# injector_C.net
KiCad netlist of a schematic drawn in EAGLE
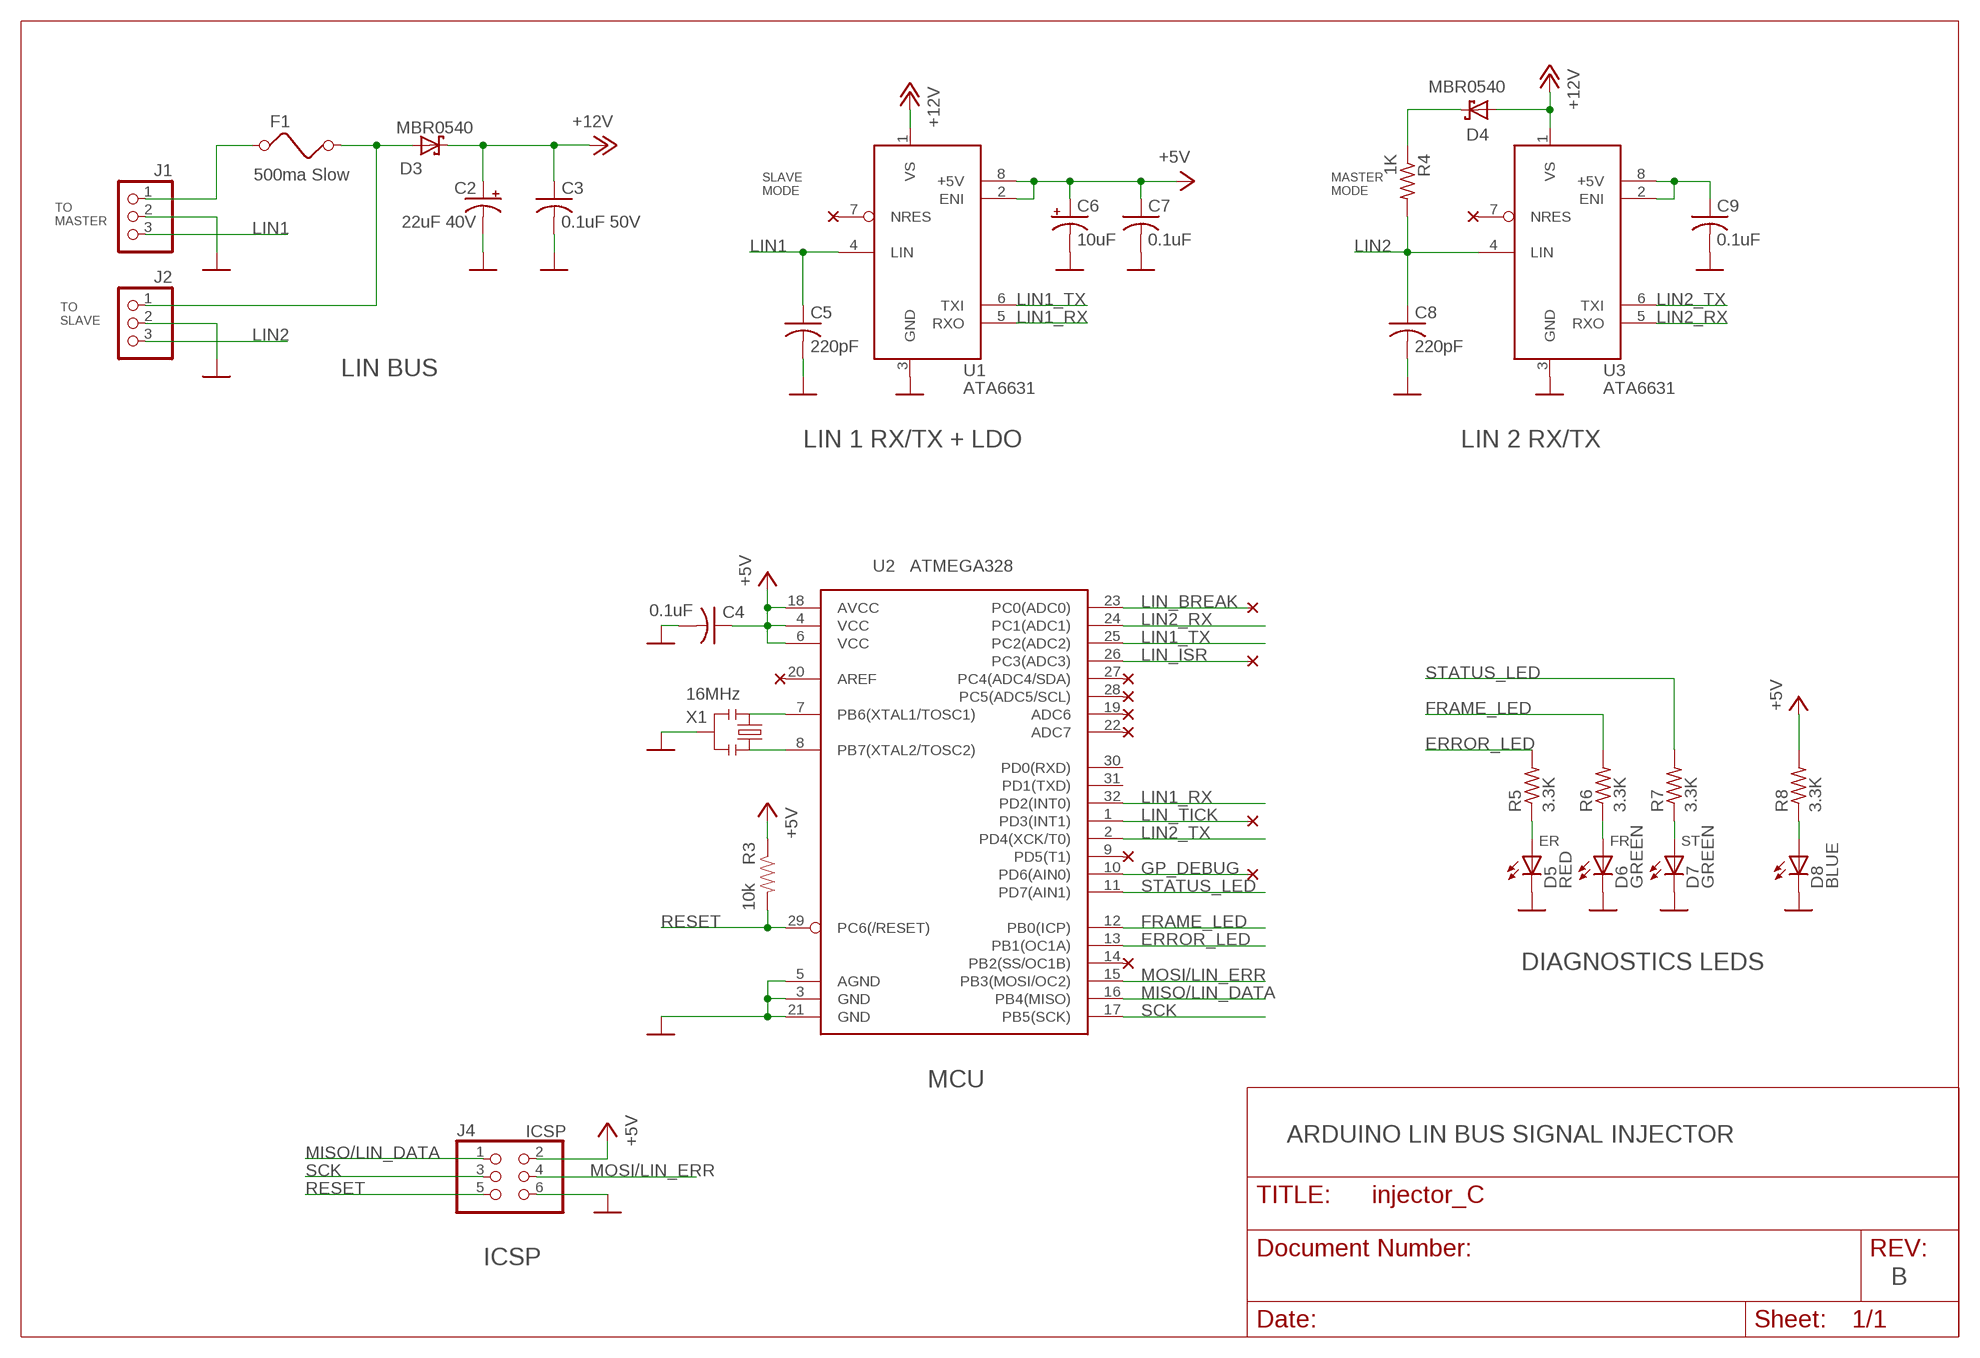
[diagram p0: schematic, sheet 1]

(export (version "E")
  (design (tool "Eeschema 10.0.6"))
  (components
    (comp (ref "C2")
      (value "22uF 40V")
      (footprint "eagle-import:UD-6,3X5,8_NICHICON")
      (libsource (lib "eagle-import") (part "CPOL-USUD-6,3X5,8"))
    )
    (comp (ref "C3")
      (value "0.1uF 50V")
      (footprint "eagle-import:C0805")
      (libsource (lib "eagle-import") (part "C-USC0805"))
    )
    (comp (ref "C4")
      (value "0.1uF")
      (footprint "eagle-import:C0805")
      (libsource (lib "eagle-import") (part "C-USC0805"))
    )
    (comp (ref "C5")
      (value "220pF")
      (footprint "eagle-import:C0805")
      (libsource (lib "eagle-import") (part "C-USC0805"))
    )
    (comp (ref "C6")
      (value "10uF")
      (footprint "eagle-import:A_3216-18R")
      (libsource (lib "eagle-import") (part "CPOL-USA/3216-18R"))
    )
    (comp (ref "C7")
      (value "0.1uF")
      (footprint "eagle-import:C0805")
      (libsource (lib "eagle-import") (part "C-USC0805"))
    )
    (comp (ref "C8")
      (value "220pF")
      (footprint "eagle-import:C0805")
      (libsource (lib "eagle-import") (part "C-USC0805"))
    )
    (comp (ref "C9")
      (value "0.1uF")
      (footprint "eagle-import:C0805")
      (libsource (lib "eagle-import") (part "C-USC0805"))
    )
    (comp (ref "D3")
      (value "MBR0540")
      (footprint "eagle-import:SOD123FL")
      (libsource (lib "eagle-import") (part "SMF5.0AT1"))
    )
    (comp (ref "D4")
      (value "MBR0540")
      (footprint "eagle-import:SOD123FL")
      (libsource (lib "eagle-import") (part "SMF5.0AT1"))
    )
    (comp (ref "D5")
      (value "RED")
      (footprint "eagle-import:1206-LED")
      (libsource (lib "eagle-import") (part "LED"))
    )
    (comp (ref "D6")
      (value "GREEN")
      (footprint "eagle-import:1206-LED")
      (libsource (lib "eagle-import") (part "LED"))
    )
    (comp (ref "D7")
      (value "GREEN")
      (footprint "eagle-import:1206-LED")
      (libsource (lib "eagle-import") (part "LED"))
    )
    (comp (ref "D8")
      (value "BLUE")
      (footprint "eagle-import:1206-LED")
      (libsource (lib "eagle-import") (part "LED"))
    )
    (comp (ref "F1")
      (value "500ma Slow")
      (footprint "eagle-import:1206")
      (libsource (lib "eagle-import") (part "FUSE"))
    )
    (comp (ref "J1")
      (value "PINHD-1X3")
      (footprint "eagle-import:1X03")
      (libsource (lib "eagle-import") (part "PINHD-1X3"))
    )
    (comp (ref "J2")
      (value "PINHD-1X3")
      (footprint "eagle-import:1X03")
      (libsource (lib "eagle-import") (part "PINHD-1X3"))
    )
    (comp (ref "J4")
      (value "ICSP")
      (footprint "eagle-import:2X03")
      (libsource (lib "eagle-import") (part "PINHD-2X3"))
    )
    (comp (ref "R3")
      (value "10k")
      (footprint "eagle-import:1206")
      (libsource (lib "eagle-import") (part "RESISTOR1206"))
    )
    (comp (ref "R4")
      (value "1K")
      (footprint "eagle-import:R0805")
      (libsource (lib "eagle-import") (part "R-US_R0805"))
    )
    (comp (ref "R5")
      (value "3.3K")
      (footprint "eagle-import:R0805")
      (libsource (lib "eagle-import") (part "R-US_R0805"))
    )
    (comp (ref "R6")
      (value "3.3K")
      (footprint "eagle-import:R0805")
      (libsource (lib "eagle-import") (part "R-US_R0805"))
    )
    (comp (ref "R7")
      (value "3.3K")
      (footprint "eagle-import:R0805")
      (libsource (lib "eagle-import") (part "R-US_R0805"))
    )
    (comp (ref "R8")
      (value "3.3K")
      (footprint "eagle-import:R0805")
      (libsource (lib "eagle-import") (part "R-US_R0805"))
    )
    (comp (ref "U1")
      (value "ATA6631")
      (footprint "eagle-import:SO-08")
      (libsource (lib "eagle-import") (part "ATA6631"))
    )
    (comp (ref "U2")
      (value "ATMEGA328")
      (footprint "eagle-import:TQFP32-08")
      (libsource (lib "eagle-import") (part "ATMEGA328"))
    )
    (comp (ref "U3")
      (value "ATA6631")
      (footprint "eagle-import:SO-08")
      (libsource (lib "eagle-import") (part "ATA6631"))
    )
    (comp (ref "X1")
      (value "16MHz")
      (footprint "eagle-import:RESONATOR-SMD")
      (libsource (lib "eagle-import") (part "RESONATORSMD"))
    )
  )
  (nets
    (net (code "1") (name "+5V") (class "Default")
      (node (ref "C4") (pin "1") (pinfunction "1_1") (pintype "passive"))
      (node (ref "C6") (pin "+") (pinfunction "+_+") (pintype "passive"))
      (node (ref "C7") (pin "1") (pinfunction "1_1") (pintype "passive"))
      (node (ref "J4") (pin "2") (pinfunction "2_2") (pintype "passive"))
      (node (ref "R3") (pin "1") (pinfunction "1_1") (pintype "passive"))
      (node (ref "R8") (pin "2") (pinfunction "2_2") (pintype "passive"))
      (node (ref "U1") (pin "2") (pinfunction "ENI_2") (pintype "input"))
      (node (ref "U1") (pin "8") (pinfunction "+5V_8") (pintype "power_in"))
      (node (ref "U2") (pin "18") (pinfunction "AVCC_18") (pintype "power_in"))
      (node (ref "U2") (pin "4") (pinfunction "VCC_4") (pintype "power_in"))
      (node (ref "U2") (pin "6") (pinfunction "VCC_6") (pintype "power_in"))
    )
    (net (code "2") (name "+12V") (class "Default")
      (node (ref "C2") (pin "+") (pinfunction "+_+") (pintype "passive"))
      (node (ref "C3") (pin "1") (pinfunction "1_1") (pintype "passive"))
      (node (ref "D3") (pin "C") (pinfunction "C_C") (pintype "passive"))
      (node (ref "D4") (pin "A") (pinfunction "A_A") (pintype "passive"))
      (node (ref "U1") (pin "1") (pinfunction "VS_1") (pintype "power_in"))
      (node (ref "U3") (pin "1") (pinfunction "VS_1") (pintype "power_in"))
    )
    (net (code "3") (name "/AREF") (class "Default")
      (node (ref "U2") (pin "20") (pinfunction "AREF_20") (pintype "power_in"))
    )
    (net (code "4") (name "/ERROR_LED") (class "Default")
      (node (ref "R5") (pin "2") (pinfunction "2_2") (pintype "passive"))
      (node (ref "U2") (pin "13") (pinfunction "PB1(OC1A)_13") (pintype "bidirectional"))
    )
    (net (code "5") (name "/FRAME_LED") (class "Default")
      (node (ref "R6") (pin "2") (pinfunction "2_2") (pintype "passive"))
      (node (ref "U2") (pin "12") (pinfunction "PB0(ICP)_12") (pintype "bidirectional"))
    )
    (net (code "6") (name "/GP_DEBUG") (class "Default")
      (node (ref "U2") (pin "10") (pinfunction "PD6(AIN0)_10") (pintype "bidirectional"))
    )
    (net (code "7") (name "/LIN1") (class "Default")
      (node (ref "C5") (pin "1") (pinfunction "1_1") (pintype "passive"))
      (node (ref "J1") (pin "3") (pinfunction "3_3") (pintype "passive"))
      (node (ref "U1") (pin "4") (pinfunction "LIN_4") (pintype "bidirectional"))
    )
    (net (code "8") (name "/LIN1_RX") (class "Default")
      (node (ref "U1") (pin "5") (pinfunction "RXO_5") (pintype "output"))
      (node (ref "U2") (pin "32") (pinfunction "PD2(INT0)_32") (pintype "bidirectional"))
    )
    (net (code "9") (name "/LIN1_TX") (class "Default")
      (node (ref "U1") (pin "6") (pinfunction "TXI_6") (pintype "input"))
      (node (ref "U2") (pin "25") (pinfunction "PC2(ADC2)_25") (pintype "bidirectional"))
    )
    (net (code "10") (name "/LIN2") (class "Default")
      (node (ref "C8") (pin "1") (pinfunction "1_1") (pintype "passive"))
      (node (ref "J2") (pin "3") (pinfunction "3_3") (pintype "passive"))
      (node (ref "R4") (pin "2") (pinfunction "2_2") (pintype "passive"))
      (node (ref "U3") (pin "4") (pinfunction "LIN_4") (pintype "bidirectional"))
    )
    (net (code "11") (name "/LIN2_RX") (class "Default")
      (node (ref "U2") (pin "24") (pinfunction "PC1(ADC1)_24") (pintype "bidirectional"))
      (node (ref "U3") (pin "5") (pinfunction "RXO_5") (pintype "output"))
    )
    (net (code "12") (name "/LIN2_TX") (class "Default")
      (node (ref "U2") (pin "2") (pinfunction "PD4(XCK/T0)_2") (pintype "bidirectional"))
      (node (ref "U3") (pin "6") (pinfunction "TXI_6") (pintype "input"))
    )
    (net (code "13") (name "/LIN_BREAK") (class "Default")
      (node (ref "U2") (pin "23") (pinfunction "PC0(ADC0)_23") (pintype "bidirectional"))
    )
    (net (code "14") (name "/LIN_ISR") (class "Default")
      (node (ref "U2") (pin "26") (pinfunction "PC3(ADC3)_26") (pintype "bidirectional"))
    )
    (net (code "15") (name "/LIN_TICK") (class "Default")
      (node (ref "U2") (pin "1") (pinfunction "PD3(INT1)_1") (pintype "bidirectional"))
    )
    (net (code "16") (name "/MISO{slash}LIN_DATA") (class "Default")
      (node (ref "J4") (pin "1") (pinfunction "1_1") (pintype "passive"))
      (node (ref "U2") (pin "16") (pinfunction "PB4(MISO)_16") (pintype "bidirectional"))
    )
    (net (code "17") (name "/MOSI{slash}LIN_ERR") (class "Default")
      (node (ref "J4") (pin "4") (pinfunction "4_4") (pintype "passive"))
      (node (ref "U2") (pin "15") (pinfunction "PB3(MOSI/OC2)_15") (pintype "bidirectional"))
    )
    (net (code "18") (name "/RESET") (class "Default")
      (node (ref "J4") (pin "5") (pinfunction "5_5") (pintype "passive"))
      (node (ref "R3") (pin "2") (pinfunction "2_2") (pintype "passive"))
      (node (ref "U2") (pin "29") (pinfunction "PC6(/RESET)_29") (pintype "bidirectional"))
    )
    (net (code "19") (name "/SCK") (class "Default")
      (node (ref "J4") (pin "3") (pinfunction "3_3") (pintype "passive"))
      (node (ref "U2") (pin "17") (pinfunction "PB5(SCK)_17") (pintype "bidirectional"))
    )
    (net (code "20") (name "/STATUS_LED") (class "Default")
      (node (ref "R7") (pin "2") (pinfunction "2_2") (pintype "passive"))
      (node (ref "U2") (pin "11") (pinfunction "PD7(AIN1)_11") (pintype "bidirectional"))
    )
    (net (code "21") (name "GND") (class "Default")
      (node (ref "C2") (pin "-") (pinfunction "-_-") (pintype "passive"))
      (node (ref "C3") (pin "2") (pinfunction "2_2") (pintype "passive"))
      (node (ref "C4") (pin "2") (pinfunction "2_2") (pintype "passive"))
      (node (ref "C5") (pin "2") (pinfunction "2_2") (pintype "passive"))
      (node (ref "C6") (pin "-") (pinfunction "-_-") (pintype "passive"))
      (node (ref "C7") (pin "2") (pinfunction "2_2") (pintype "passive"))
      (node (ref "C8") (pin "2") (pinfunction "2_2") (pintype "passive"))
      (node (ref "C9") (pin "2") (pinfunction "2_2") (pintype "passive"))
      (node (ref "D5") (pin "C") (pinfunction "C_C") (pintype "passive"))
      (node (ref "D6") (pin "C") (pinfunction "C_C") (pintype "passive"))
      (node (ref "D7") (pin "C") (pinfunction "C_C") (pintype "passive"))
      (node (ref "D8") (pin "C") (pinfunction "C_C") (pintype "passive"))
      (node (ref "J1") (pin "2") (pinfunction "2_2") (pintype "passive"))
      (node (ref "J2") (pin "2") (pinfunction "2_2") (pintype "passive"))
      (node (ref "J4") (pin "6") (pinfunction "6_6") (pintype "passive"))
      (node (ref "U1") (pin "3") (pinfunction "GND_3") (pintype "power_in"))
      (node (ref "U2") (pin "21") (pinfunction "GND_21") (pintype "power_in"))
      (node (ref "U2") (pin "3") (pinfunction "GND_3") (pintype "power_in"))
      (node (ref "U2") (pin "5") (pinfunction "AGND_5") (pintype "power_in"))
      (node (ref "U3") (pin "3") (pinfunction "GND_3") (pintype "power_in"))
      (node (ref "X1") (pin "2") (pinfunction "2_2") (pintype "passive"))
    )
    (net (code "22") (name "Net-(D3-PadA)") (class "Default")
      (node (ref "D3") (pin "A") (pinfunction "A_A") (pintype "passive"))
      (node (ref "F1") (pin "2") (pinfunction "2_2") (pintype "passive"))
      (node (ref "J2") (pin "1") (pinfunction "1_1") (pintype "passive"))
    )
    (net (code "23") (name "Net-(D4-PadC)") (class "Default")
      (node (ref "D4") (pin "C") (pinfunction "C_C") (pintype "passive"))
      (node (ref "R4") (pin "1") (pinfunction "1_1") (pintype "passive"))
    )
    (net (code "24") (name "Net-(D5-PadA)") (class "Default")
      (node (ref "D5") (pin "A") (pinfunction "A_A") (pintype "passive"))
      (node (ref "R5") (pin "1") (pinfunction "1_1") (pintype "passive"))
    )
    (net (code "25") (name "Net-(D6-PadA)") (class "Default")
      (node (ref "D6") (pin "A") (pinfunction "A_A") (pintype "passive"))
      (node (ref "R6") (pin "1") (pinfunction "1_1") (pintype "passive"))
    )
    (net (code "26") (name "Net-(D7-PadA)") (class "Default")
      (node (ref "D7") (pin "A") (pinfunction "A_A") (pintype "passive"))
      (node (ref "R7") (pin "1") (pinfunction "1_1") (pintype "passive"))
    )
    (net (code "27") (name "Net-(D8-PadA)") (class "Default")
      (node (ref "D8") (pin "A") (pinfunction "A_A") (pintype "passive"))
      (node (ref "R8") (pin "1") (pinfunction "1_1") (pintype "passive"))
    )
    (net (code "28") (name "Net-(F1-Pad1)") (class "Default")
      (node (ref "F1") (pin "1") (pinfunction "1_1") (pintype "passive"))
      (node (ref "J1") (pin "1") (pinfunction "1_1") (pintype "passive"))
    )
    (net (code "29") (name "Net-(U2-PB6(XTAL1{slash}TOSC1))") (class "Default")
      (node (ref "U2") (pin "7") (pinfunction "PB6(XTAL1/TOSC1)_7") (pintype "bidirectional"))
      (node (ref "X1") (pin "3") (pinfunction "3_3") (pintype "passive"))
    )
    (net (code "30") (name "Net-(U2-PB7(XTAL2{slash}TOSC2))") (class "Default")
      (node (ref "U2") (pin "8") (pinfunction "PB7(XTAL2/TOSC2)_8") (pintype "bidirectional"))
      (node (ref "X1") (pin "1") (pinfunction "1_1") (pintype "passive"))
    )
    (net (code "31") (name "Net-(U3-+5V)") (class "Default")
      (node (ref "C9") (pin "1") (pinfunction "1_1") (pintype "passive"))
      (node (ref "U3") (pin "2") (pinfunction "ENI_2") (pintype "input"))
      (node (ref "U3") (pin "8") (pinfunction "+5V_8") (pintype "power_in"))
    )
    (net (code "32") (name "unconnected-(U1-NRES-Pad7)") (class "Default")
      (node (ref "U1") (pin "7") (pinfunction "NRES_7") (pintype "output"))
    )
    (net (code "33") (name "unconnected-(U2-ADC6-Pad19)") (class "Default")
      (node (ref "U2") (pin "19") (pinfunction "ADC6_19") (pintype "bidirectional"))
    )
    (net (code "34") (name "unconnected-(U2-ADC7-Pad22)") (class "Default")
      (node (ref "U2") (pin "22") (pinfunction "ADC7_22") (pintype "bidirectional"))
    )
    (net (code "35") (name "unconnected-(U2-PB2(SS{slash}OC1B)-Pad14)") (class "Default")
      (node (ref "U2") (pin "14") (pinfunction "PB2(SS/OC1B)_14") (pintype "bidirectional"))
    )
    (net (code "36") (name "unconnected-(U2-PC4(ADC4{slash}SDA)-Pad27)") (class "Default")
      (node (ref "U2") (pin "27") (pinfunction "PC4(ADC4/SDA)_27") (pintype "bidirectional"))
    )
    (net (code "37") (name "unconnected-(U2-PC5(ADC5{slash}SCL)-Pad28)") (class "Default")
      (node (ref "U2") (pin "28") (pinfunction "PC5(ADC5/SCL)_28") (pintype "bidirectional"))
    )
    (net (code "38") (name "unconnected-(U2-PD0(RXD)-Pad30)") (class "Default")
      (node (ref "U2") (pin "30") (pinfunction "PD0(RXD)_30") (pintype "bidirectional"))
    )
    (net (code "39") (name "unconnected-(U2-PD1(TXD)-Pad31)") (class "Default")
      (node (ref "U2") (pin "31") (pinfunction "PD1(TXD)_31") (pintype "bidirectional"))
    )
    (net (code "40") (name "unconnected-(U2-PD5(T1)-Pad9)") (class "Default")
      (node (ref "U2") (pin "9") (pinfunction "PD5(T1)_9") (pintype "bidirectional"))
    )
    (net (code "41") (name "unconnected-(U3-NRES-Pad7)") (class "Default")
      (node (ref "U3") (pin "7") (pinfunction "NRES_7") (pintype "output"))
    )
  )
)
